# eFuse.net
KiCad netlist of a schematic drawn in Altium Designer
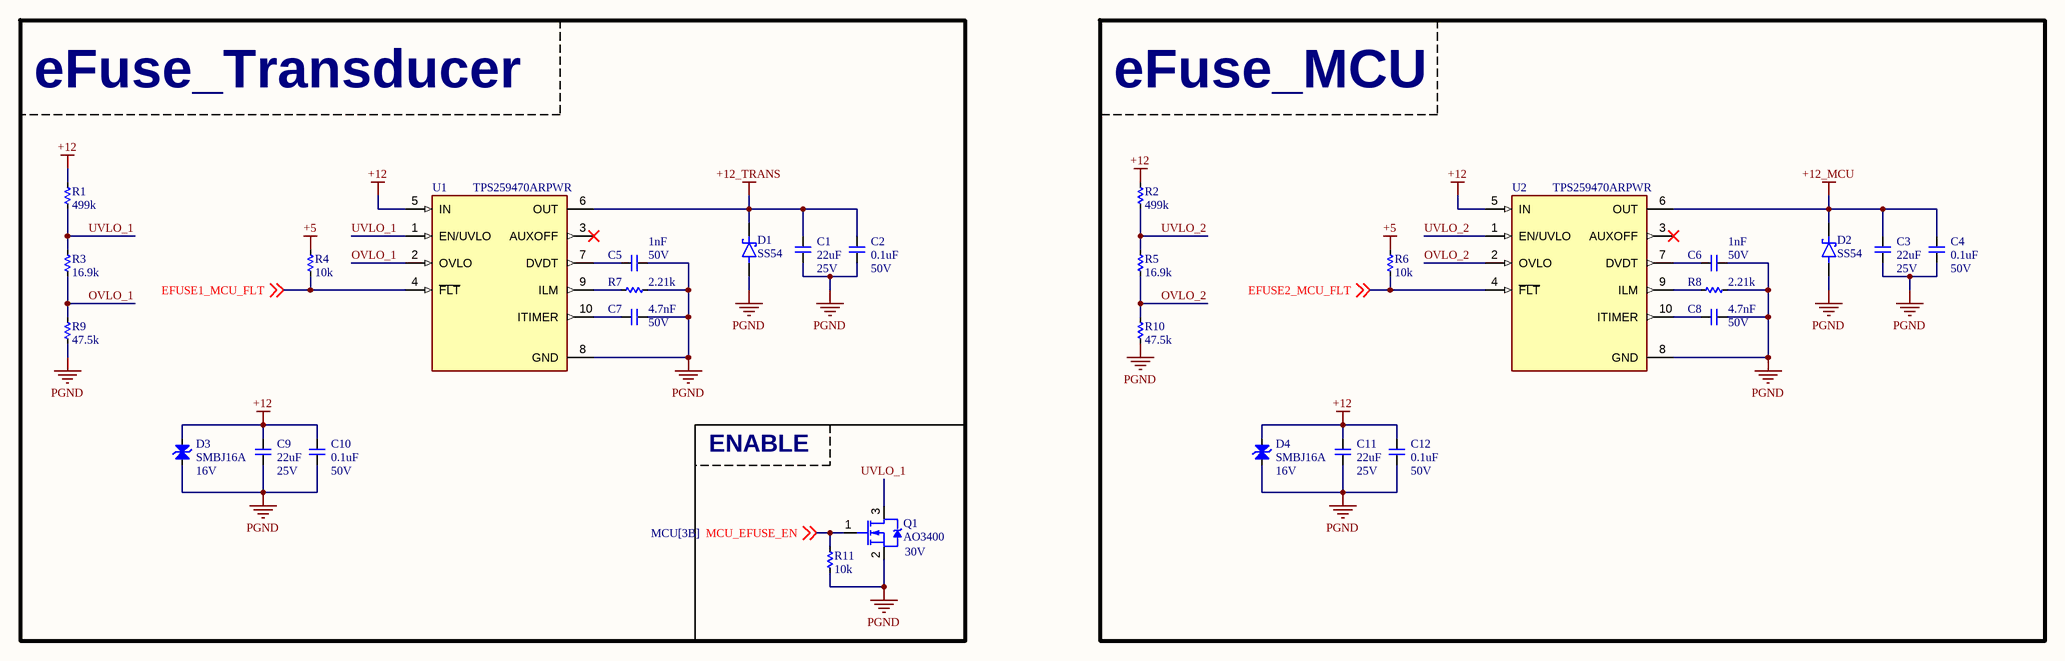
[diagram p0: eFuse.SchDoc]

(export (version "E")
  (design (tool "Eeschema 10.0.6"))
  (components
    (comp (ref "C1")
      (value "22uF")
      (footprint "CAP_C_2012X110")
      (description "CAP")
      (fields (field (name "VOLTAGE") "25V"))
      (libsource (lib "LABLIB") (part "_CAP_C_2"))
    )
    (comp (ref "C2")
      (value "0.1uF")
      (footprint "CAP_C_1608X80")
      (description "CAP")
      (fields (field (name "VOLTAGE") "50V"))
      (libsource (lib "LABLIB") (part "_CAP_C_2"))
    )
    (comp (ref "C3")
      (value "22uF")
      (footprint "CAP_C_2012X110")
      (description "CAP")
      (fields (field (name "VOLTAGE") "25V"))
      (libsource (lib "LABLIB") (part "_CAP_C_2"))
    )
    (comp (ref "C4")
      (value "0.1uF")
      (footprint "CAP_C_1608X80")
      (description "CAP")
      (fields (field (name "VOLTAGE") "50V"))
      (libsource (lib "LABLIB") (part "_CAP_C_2"))
    )
    (comp (ref "C5")
      (value "1nF")
      (footprint "CAP_C_1608X80")
      (description "CAP")
      (fields (field (name "VOLTAGE") "50V"))
      (libsource (lib "LABLIB") (part "_CAP_C_2"))
    )
    (comp (ref "C6")
      (value "1nF")
      (footprint "CAP_C_1608X80")
      (description "CAP")
      (fields (field (name "VOLTAGE") "50V"))
      (libsource (lib "LABLIB") (part "_CAP_C_2"))
    )
    (comp (ref "C7")
      (value "4.7nF")
      (footprint "CAP_C_1608X80")
      (description "CAP")
      (fields (field (name "VOLTAGE") "50V"))
      (libsource (lib "LABLIB") (part "_CAP_C_2"))
    )
    (comp (ref "C8")
      (value "4.7nF")
      (footprint "CAP_C_1608X80")
      (description "CAP")
      (fields (field (name "VOLTAGE") "50V"))
      (libsource (lib "LABLIB") (part "_CAP_C_2"))
    )
    (comp (ref "C9")
      (value "22uF")
      (footprint "CAP_C_2012X110")
      (description "CAP")
      (fields (field (name "VOLTAGE") "25V"))
      (libsource (lib "LABLIB") (part "_CAP_C_2"))
    )
    (comp (ref "C10")
      (value "0.1uF")
      (footprint "CAP_C_1608X80")
      (description "CAP")
      (fields (field (name "VOLTAGE") "50V"))
      (libsource (lib "LABLIB") (part "_CAP_C_2"))
    )
    (comp (ref "C11")
      (value "22uF")
      (footprint "CAP_C_2012X110")
      (description "CAP")
      (fields (field (name "VOLTAGE") "25V"))
      (libsource (lib "LABLIB") (part "_CAP_C_2"))
    )
    (comp (ref "C12")
      (value "0.1uF")
      (footprint "CAP_C_1608X80")
      (description "CAP")
      (fields (field (name "VOLTAGE") "50V"))
      (libsource (lib "LABLIB") (part "_CAP_C_2"))
    )
    (comp (ref "D1")
      (value "SS54")
      (footprint "DO-214AC_SMA")
      (description "DIODE SCHOTTKY")
      (libsource (lib "LABLIB") (part "DIODE SCHOTTKY"))
    )
    (comp (ref "D2")
      (value "SS54")
      (footprint "DO-214AC_SMA")
      (description "DIODE SCHOTTKY")
      (libsource (lib "LABLIB") (part "DIODE SCHOTTKY"))
    )
    (comp (ref "D3")
      (value "SMBJ16A")
      (footprint "DO-214AA_SMB")
      (description "TVS Diode")
      (fields (field (name "VOLTAGE") "16V") (field (name "PUBLISHER") "Altium Limited"))
      (libsource (lib "LABLIB") (part "Diode TVS"))
    )
    (comp (ref "D4")
      (value "SMBJ16A")
      (footprint "DO-214AA_SMB")
      (description "TVS Diode")
      (fields (field (name "VOLTAGE") "16V") (field (name "PUBLISHER") "Altium Limited"))
      (libsource (lib "LABLIB") (part "Diode TVS"))
    )
    (comp (ref "Q1")
      (value "AO3400")
      (footprint "SOT-23")
      (description "Mosfet N")
      (fields (field (name "VOLTAGE") "30V"))
      (libsource (lib "KIENASIY123_LIB") (part "Mosfet N"))
    )
    (comp (ref "R1")
      (value "499k")
      (footprint "RES_C_1608X60")
      (description "RES")
      (libsource (lib "LABLIB") (part "_RES_B_2_2"))
    )
    (comp (ref "R2")
      (value "499k")
      (footprint "RES_C_1608X60")
      (description "RES")
      (libsource (lib "LABLIB") (part "_RES_B_2_2"))
    )
    (comp (ref "R3")
      (value "16.9k")
      (footprint "RES_C_1608X60")
      (description "RES")
      (libsource (lib "LABLIB") (part "_RES_B_2_2"))
    )
    (comp (ref "R4")
      (value "10k")
      (footprint "RES_C_1608X60")
      (description "RES")
      (libsource (lib "LABLIB") (part "_RES_B_2_2"))
    )
    (comp (ref "R5")
      (value "16.9k")
      (footprint "RES_C_1608X60")
      (description "RES")
      (libsource (lib "LABLIB") (part "_RES_B_2_2"))
    )
    (comp (ref "R6")
      (value "10k")
      (footprint "RES_C_1608X60")
      (description "RES")
      (libsource (lib "LABLIB") (part "_RES_B_2_2"))
    )
    (comp (ref "R7")
      (value "2.21k")
      (footprint "RES_C_1608X60")
      (description "RES")
      (libsource (lib "LABLIB") (part "_RES_B_2_2"))
    )
    (comp (ref "R8")
      (value "2.21k")
      (footprint "RES_C_1608X60")
      (description "RES")
      (libsource (lib "LABLIB") (part "_RES_B_2_2"))
    )
    (comp (ref "R9")
      (value "47.5k")
      (footprint "RES_C_1608X60")
      (description "RES")
      (libsource (lib "LABLIB") (part "_RES_B_2_2"))
    )
    (comp (ref "R10")
      (value "47.5k")
      (footprint "RES_C_1608X60")
      (description "RES")
      (libsource (lib "LABLIB") (part "_RES_B_2_2"))
    )
    (comp (ref "R11")
      (value "10k")
      (footprint "RES_C_1608X60")
      (description "RES")
      (libsource (lib "LABLIB") (part "_RES_B_2_2"))
    )
    (comp (ref "U1")
      (value "TPS259470ARPWR")
      (footprint "TPS259474")
      (libsource (lib "new1") (part "TPS259470ARPWR"))
    )
    (comp (ref "U2")
      (value "TPS259470ARPWR")
      (footprint "TPS259474")
      (libsource (lib "new1") (part "TPS259470ARPWR"))
    )
  )
  (nets
    (net (code "1") (name "+5") (class "Default")
      (node (ref "R4") (pin "1") (pinfunction "1_1") (pintype "passive"))
      (node (ref "R6") (pin "1") (pinfunction "1_1") (pintype "passive"))
    )
    (net (code "2") (name "+12") (class "Default")
      (node (ref "C10") (pin "2") (pinfunction "2_2") (pintype "passive"))
      (node (ref "C11") (pin "2") (pinfunction "2_2") (pintype "passive"))
      (node (ref "C12") (pin "2") (pinfunction "2_2") (pintype "passive"))
      (node (ref "C9") (pin "2") (pinfunction "2_2") (pintype "passive"))
      (node (ref "D3") (pin "1") (pinfunction "A_1") (pintype "passive"))
      (node (ref "D4") (pin "1") (pinfunction "A_1") (pintype "passive"))
      (node (ref "R1") (pin "2") (pinfunction "2_2") (pintype "passive"))
      (node (ref "R2") (pin "2") (pinfunction "2_2") (pintype "passive"))
      (node (ref "U1") (pin "5") (pinfunction "IN_5") (pintype "input"))
      (node (ref "U2") (pin "5") (pinfunction "IN_5") (pintype "input"))
    )
    (net (code "3") (name "+12_MCU") (class "Default")
      (node (ref "C3") (pin "2") (pinfunction "2_2") (pintype "passive"))
      (node (ref "C4") (pin "1") (pinfunction "1_1") (pintype "passive"))
      (node (ref "D2") (pin "1") (pinfunction "K_1") (pintype "passive"))
      (node (ref "U2") (pin "6") (pinfunction "OUT_6") (pintype "power_in"))
    )
    (net (code "4") (name "+12_TRANS") (class "Default")
      (node (ref "C1") (pin "2") (pinfunction "2_2") (pintype "passive"))
      (node (ref "C2") (pin "1") (pinfunction "1_1") (pintype "passive"))
      (node (ref "D1") (pin "1") (pinfunction "K_1") (pintype "passive"))
      (node (ref "U1") (pin "6") (pinfunction "OUT_6") (pintype "power_in"))
    )
    (net (code "5") (name "/OVLO_1") (class "Default")
      (node (ref "R3") (pin "1") (pinfunction "1_1") (pintype "passive"))
      (node (ref "R9") (pin "2") (pinfunction "2_2") (pintype "passive"))
      (node (ref "U1") (pin "2") (pinfunction "OVLO_2") (pintype "input"))
    )
    (net (code "6") (name "/OVLO_2") (class "Default")
      (node (ref "R10") (pin "2") (pinfunction "2_2") (pintype "passive"))
      (node (ref "R5") (pin "1") (pinfunction "1_1") (pintype "passive"))
      (node (ref "U2") (pin "2") (pinfunction "OVLO_2") (pintype "input"))
    )
    (net (code "7") (name "/UVLO_1") (class "Default")
      (node (ref "Q1") (pin "3") (pinfunction "D_3") (pintype "passive"))
      (node (ref "R1") (pin "1") (pinfunction "1_1") (pintype "passive"))
      (node (ref "R3") (pin "2") (pinfunction "2_2") (pintype "passive"))
      (node (ref "U1") (pin "1") (pinfunction "EN/UVLO_1") (pintype "input"))
    )
    (net (code "8") (name "/UVLO_2") (class "Default")
      (node (ref "R2") (pin "1") (pinfunction "1_1") (pintype "passive"))
      (node (ref "R5") (pin "2") (pinfunction "2_2") (pintype "passive"))
      (node (ref "U2") (pin "1") (pinfunction "EN/UVLO_1") (pintype "input"))
    )
    (net (code "9") (name "EFUSE1_MCU_FLT") (class "Default")
      (node (ref "R4") (pin "2") (pinfunction "2_2") (pintype "passive"))
      (node (ref "U1") (pin "4") (pinfunction "~{FLT}_4") (pintype "input"))
    )
    (net (code "10") (name "EFUSE2_MCU_FLT") (class "Default")
      (node (ref "R6") (pin "2") (pinfunction "2_2") (pintype "passive"))
      (node (ref "U2") (pin "4") (pinfunction "~{FLT}_4") (pintype "input"))
    )
    (net (code "11") (name "MCU_EFUSE_EN") (class "Default")
      (node (ref "Q1") (pin "1") (pinfunction "G_1") (pintype "passive"))
      (node (ref "R11") (pin "1") (pinfunction "1_1") (pintype "passive"))
    )
    (net (code "12") (name "Net-(U1-DVDT)") (class "Default")
      (node (ref "C5") (pin "1") (pinfunction "1_1") (pintype "passive"))
      (node (ref "U1") (pin "7") (pinfunction "DVDT_7") (pintype "output"))
    )
    (net (code "13") (name "Net-(U1-ILM)") (class "Default")
      (node (ref "R7") (pin "1") (pinfunction "1_1") (pintype "passive"))
      (node (ref "U1") (pin "9") (pinfunction "ILM_9") (pintype "output"))
    )
    (net (code "14") (name "Net-(U1-ITIMER)") (class "Default")
      (node (ref "C7") (pin "1") (pinfunction "1_1") (pintype "passive"))
      (node (ref "U1") (pin "10") (pinfunction "ITIMER_10") (pintype "output"))
    )
    (net (code "15") (name "Net-(U2-DVDT)") (class "Default")
      (node (ref "C6") (pin "1") (pinfunction "1_1") (pintype "passive"))
      (node (ref "U2") (pin "7") (pinfunction "DVDT_7") (pintype "output"))
    )
    (net (code "16") (name "Net-(U2-ILM)") (class "Default")
      (node (ref "R8") (pin "1") (pinfunction "1_1") (pintype "passive"))
      (node (ref "U2") (pin "9") (pinfunction "ILM_9") (pintype "output"))
    )
    (net (code "17") (name "Net-(U2-ITIMER)") (class "Default")
      (node (ref "C8") (pin "1") (pinfunction "1_1") (pintype "passive"))
      (node (ref "U2") (pin "10") (pinfunction "ITIMER_10") (pintype "output"))
    )
    (net (code "18") (name "PGND") (class "Default")
      (node (ref "C1") (pin "1") (pinfunction "1_1") (pintype "passive"))
      (node (ref "C10") (pin "1") (pinfunction "1_1") (pintype "passive"))
      (node (ref "C11") (pin "1") (pinfunction "1_1") (pintype "passive"))
      (node (ref "C12") (pin "1") (pinfunction "1_1") (pintype "passive"))
      (node (ref "C2") (pin "2") (pinfunction "2_2") (pintype "passive"))
      (node (ref "C3") (pin "1") (pinfunction "1_1") (pintype "passive"))
      (node (ref "C4") (pin "2") (pinfunction "2_2") (pintype "passive"))
      (node (ref "C5") (pin "2") (pinfunction "2_2") (pintype "passive"))
      (node (ref "C6") (pin "2") (pinfunction "2_2") (pintype "passive"))
      (node (ref "C7") (pin "2") (pinfunction "2_2") (pintype "passive"))
      (node (ref "C8") (pin "2") (pinfunction "2_2") (pintype "passive"))
      (node (ref "C9") (pin "1") (pinfunction "1_1") (pintype "passive"))
      (node (ref "D1") (pin "2") (pinfunction "A_2") (pintype "passive"))
      (node (ref "D2") (pin "2") (pinfunction "A_2") (pintype "passive"))
      (node (ref "D3") (pin "2") (pinfunction "K_2") (pintype "passive"))
      (node (ref "D4") (pin "2") (pinfunction "K_2") (pintype "passive"))
      (node (ref "Q1") (pin "2") (pinfunction "S_2") (pintype "passive"))
      (node (ref "R10") (pin "1") (pinfunction "1_1") (pintype "passive"))
      (node (ref "R11") (pin "2") (pinfunction "2_2") (pintype "passive"))
      (node (ref "R7") (pin "2") (pinfunction "2_2") (pintype "passive"))
      (node (ref "R8") (pin "2") (pinfunction "2_2") (pintype "passive"))
      (node (ref "R9") (pin "1") (pinfunction "1_1") (pintype "passive"))
      (node (ref "U1") (pin "8") (pinfunction "GND_8") (pintype "power_in"))
      (node (ref "U2") (pin "8") (pinfunction "GND_8") (pintype "power_in"))
    )
    (net (code "19") (name "unconnected-(U1-AUXOFF-Pad3)") (class "Default")
      (node (ref "U1") (pin "3") (pinfunction "AUXOFF_3") (pintype "output+no_connect"))
    )
    (net (code "20") (name "unconnected-(U2-AUXOFF-Pad3)") (class "Default")
      (node (ref "U2") (pin "3") (pinfunction "AUXOFF_3") (pintype "output+no_connect"))
    )
  )
)
